# LAMEBOY.net
KiCad netlist of a schematic drawn in EAGLE
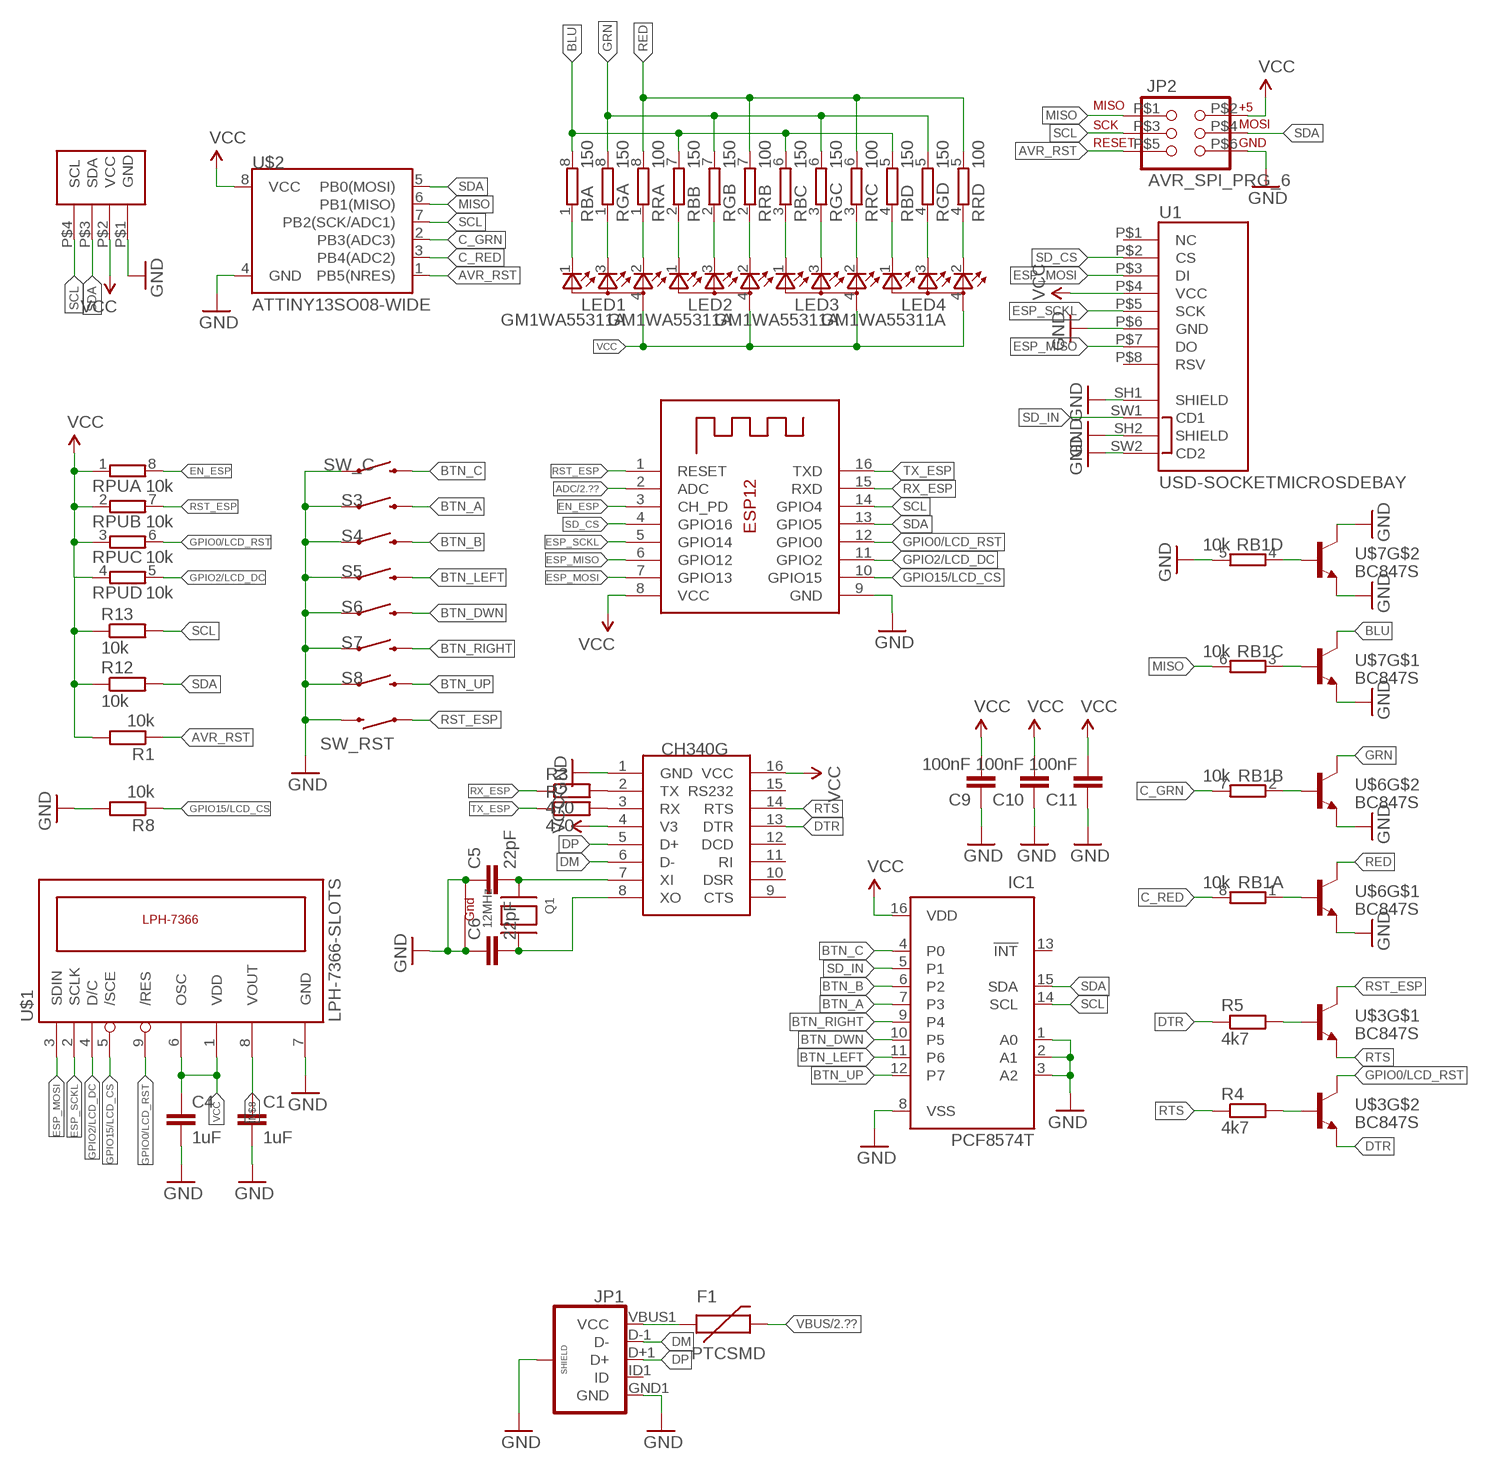
[diagram p0: schematic, sheet 1]
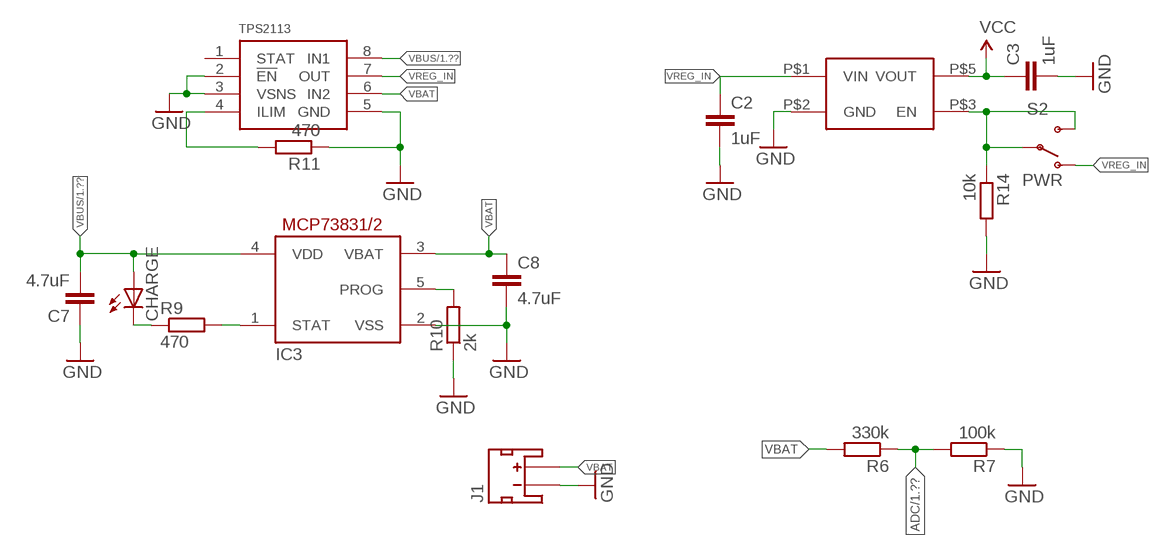
[diagram p1: schematic, sheet 2]

(export (version "E")
  (design (tool "Eeschema 10.0.6"))
  (components
    (comp (ref "C2")
      (value "1uF")
      (footprint "eagle-import:ONEFITSALL")
      (libsource (lib "eagle-import") (part "C-EUONEFITSALL"))
    )
    (comp (ref "C3")
      (value "1uF")
      (footprint "eagle-import:ONEFITSALL")
      (libsource (lib "eagle-import") (part "C-EUONEFITSALL"))
    )
    (comp (ref "C7")
      (value "4.7uF")
      (footprint "eagle-import:ONEFITSALL")
      (libsource (lib "eagle-import") (part "C-EUONEFITSALL"))
    )
    (comp (ref "C8")
      (value "4.7uF")
      (footprint "eagle-import:ONEFITSALL")
      (libsource (lib "eagle-import") (part "C-EUONEFITSALL"))
    )
    (comp (ref "CHARGE")
      (value "LEDCHARLIE")
      (footprint "eagle-import:CHIPLED_0603_CHARLIE")
      (libsource (lib "eagle-import") (part "LEDCHARLIE"))
    )
    (comp (ref "IC3")
      (value "MCP73831")
      (footprint "eagle-import:SOT23-5L")
      (libsource (lib "eagle-import") (part "MCP73831/OT"))
    )
    (comp (ref "J1")
      (value "JST_2MM_MALE")
      (footprint "eagle-import:JST-2-SMD")
      (libsource (lib "eagle-import") (part "JST_2MM_MALE"))
    )
    (comp (ref "R6")
      (value "330k")
      (footprint "eagle-import:ONEFITSALL")
      (libsource (lib "eagle-import") (part "R-EU_ONEFITSALL"))
    )
    (comp (ref "R7")
      (value "100k")
      (footprint "eagle-import:ONEFITSALL")
      (libsource (lib "eagle-import") (part "R-EU_ONEFITSALL"))
    )
    (comp (ref "R9")
      (value "470")
      (footprint "eagle-import:ONEFITSALL")
      (libsource (lib "eagle-import") (part "R-EU_ONEFITSALL"))
    )
    (comp (ref "R10")
      (value "2k")
      (footprint "eagle-import:ONEFITSALL")
      (libsource (lib "eagle-import") (part "R-EU_ONEFITSALL"))
    )
    (comp (ref "R11")
      (value "470")
      (footprint "eagle-import:ONEFITSALL")
      (libsource (lib "eagle-import") (part "R-EU_ONEFITSALL"))
    )
    (comp (ref "R14")
      (value "10k")
      (footprint "eagle-import:ONEFITSALL")
      (libsource (lib "eagle-import") (part "R-EU_ONEFITSALL"))
    )
    (comp (ref "S2")
      (value "PWR")
      (footprint "eagle-import:SWITCH-SPST-SMD-A")
      (libsource (lib "eagle-import") (part "SWITCH-SPDT-SMD-A"))
    )
    (comp (ref "U$4")
      (value "TPS2113-PW")
      (footprint "eagle-import:TEXAS-PW")
      (libsource (lib "eagle-import") (part "TPS2113-PW"))
    )
    (comp (ref "U$9")
      (value "AP2112KAP2112K")
      (footprint "eagle-import:AP2112")
      (libsource (lib "eagle-import") (part "AP2112KAP2112K"))
    )
    (comp (ref "C1")
      (value "1uF")
      (footprint "eagle-import:ONEFITSALL")
      (libsource (lib "eagle-import") (part "C-EUONEFITSALL"))
    )
    (comp (ref "C4")
      (value "1uF")
      (footprint "eagle-import:ONEFITSALL")
      (libsource (lib "eagle-import") (part "C-EUONEFITSALL"))
    )
    (comp (ref "C5")
      (value "22pF")
      (footprint "eagle-import:ONEFITSALL")
      (libsource (lib "eagle-import") (part "C-EUONEFITSALL"))
    )
    (comp (ref "C6")
      (value "22pF")
      (footprint "eagle-import:ONEFITSALL")
      (libsource (lib "eagle-import") (part "C-EUONEFITSALL"))
    )
    (comp (ref "C9")
      (value "100nF")
      (footprint "eagle-import:ONEFITSALL")
      (libsource (lib "eagle-import") (part "C-EUONEFITSALL"))
    )
    (comp (ref "C10")
      (value "100nF")
      (footprint "eagle-import:ONEFITSALL")
      (libsource (lib "eagle-import") (part "C-EUONEFITSALL"))
    )
    (comp (ref "C11")
      (value "100nF")
      (footprint "eagle-import:ONEFITSALL")
      (libsource (lib "eagle-import") (part "C-EUONEFITSALL"))
    )
    (comp (ref "CH340G")
      (value "CH340GCH340G")
      (footprint "eagle-import:SOIC16")
      (libsource (lib "eagle-import") (part "CH340GCH340G"))
    )
    (comp (ref "F1")
      (value "PTCSMD")
      (footprint "eagle-import:PTC-1206")
      (libsource (lib "eagle-import") (part "PTCSMD"))
    )
    (comp (ref "IC1")
      (value "PCF8574T")
      (footprint "eagle-import:SO16W")
      (fields (field (name "MPN") "PCF8574T/3,512"))
      (libsource (lib "eagle-import") (part "PCF8574T"))
    )
    (comp (ref "JP1")
      (value "USB_MICROB_PLUG-IDK")
      (footprint "eagle-import:USB-AB-MICRO-SMD_SLOT")
      (libsource (lib "eagle-import") (part "USB_MICROB_PLUG-IDK"))
    )
    (comp (ref "JP2")
      (value "AVR_SPI_PRG_6")
      (footprint "eagle-import:2X3_SMD_PAD")
      (libsource (lib "eagle-import") (part "AVR_SPI_PRG_6"))
    )
    (comp (ref "LED1")
      (value "GM1WA55311A")
      (footprint "eagle-import:GM1WA55311A")
      (libsource (lib "eagle-import") (part "GM1WA55311A"))
    )
    (comp (ref "LED2")
      (value "GM1WA55311A")
      (footprint "eagle-import:GM1WA55311A")
      (libsource (lib "eagle-import") (part "GM1WA55311A"))
    )
    (comp (ref "LED3")
      (value "GM1WA55311A")
      (footprint "eagle-import:GM1WA55311A")
      (libsource (lib "eagle-import") (part "GM1WA55311A"))
    )
    (comp (ref "LED4")
      (value "GM1WA55311A")
      (footprint "eagle-import:GM1WA55311A")
      (libsource (lib "eagle-import") (part "GM1WA55311A"))
    )
    (comp (ref "Q1")
      (value "12MHz")
      (footprint "eagle-import:NX3225_BIGGER")
      (libsource (lib "eagle-import") (part "XTAL-4BIGGER"))
    )
    (comp (ref "R1")
      (value "10k")
      (footprint "eagle-import:ONEFITSALL")
      (libsource (lib "eagle-import") (part "R-EU_ONEFITSALL"))
    )
    (comp (ref "R2")
      (value "470")
      (footprint "eagle-import:ONEFITSALL")
      (libsource (lib "eagle-import") (part "R-EU_ONEFITSALL"))
    )
    (comp (ref "R3")
      (value "470")
      (footprint "eagle-import:ONEFITSALL")
      (libsource (lib "eagle-import") (part "R-EU_ONEFITSALL"))
    )
    (comp (ref "R4")
      (value "4k7")
      (footprint "eagle-import:ONEFITSALL")
      (libsource (lib "eagle-import") (part "R-EU_ONEFITSALL"))
    )
    (comp (ref "R5")
      (value "4k7")
      (footprint "eagle-import:ONEFITSALL")
      (libsource (lib "eagle-import") (part "R-EU_ONEFITSALL"))
    )
    (comp (ref "R8")
      (value "10k")
      (footprint "eagle-import:ONEFITSALL")
      (libsource (lib "eagle-import") (part "R-EU_ONEFITSALL"))
    )
    (comp (ref "R12")
      (value "10k")
      (footprint "eagle-import:ONEFITSALL")
      (libsource (lib "eagle-import") (part "R-EU_ONEFITSALL"))
    )
    (comp (ref "R13")
      (value "10k")
      (footprint "eagle-import:ONEFITSALL")
      (libsource (lib "eagle-import") (part "R-EU_ONEFITSALL"))
    )
    (comp (ref "RB")
      (value "150")
      (footprint "eagle-import:0603-ARC")
      (libsource (lib "eagle-import") (part "4R-N0603-ARC"))
    )
    (comp (ref "RB1")
      (value "10k")
      (footprint "eagle-import:0603-ARC")
      (libsource (lib "eagle-import") (part "4R-N0603-ARC"))
    )
    (comp (ref "RG")
      (value "150")
      (footprint "eagle-import:0603-ARC")
      (libsource (lib "eagle-import") (part "4R-N0603-ARC"))
    )
    (comp (ref "RPU")
      (value "10k")
      (footprint "eagle-import:0603-ARC")
      (libsource (lib "eagle-import") (part "4R-N0603-ARC"))
    )
    (comp (ref "RR")
      (value "100")
      (footprint "eagle-import:0603-ARC")
      (libsource (lib "eagle-import") (part "4R-N0603-ARC"))
    )
    (comp (ref "S3")
      (value "SWITCH-MOMENTARY-2SMD-4")
      (footprint "eagle-import:TACTILE_SWITCH_TALL")
      (libsource (lib "eagle-import") (part "SWITCH-MOMENTARY-2SMD-4"))
    )
    (comp (ref "S4")
      (value "SWITCH-MOMENTARY-2SMD-4")
      (footprint "eagle-import:TACTILE_SWITCH_TALL")
      (libsource (lib "eagle-import") (part "SWITCH-MOMENTARY-2SMD-4"))
    )
    (comp (ref "S5")
      (value "SWITCH-MOMENTARY-2SMD-4")
      (footprint "eagle-import:TACTILE_SWITCH_TALL")
      (libsource (lib "eagle-import") (part "SWITCH-MOMENTARY-2SMD-4"))
    )
    (comp (ref "S6")
      (value "SWITCH-MOMENTARY-2SMD-4")
      (footprint "eagle-import:TACTILE_SWITCH_TALL")
      (libsource (lib "eagle-import") (part "SWITCH-MOMENTARY-2SMD-4"))
    )
    (comp (ref "S7")
      (value "SWITCH-MOMENTARY-2SMD-4")
      (footprint "eagle-import:TACTILE_SWITCH_TALL")
      (libsource (lib "eagle-import") (part "SWITCH-MOMENTARY-2SMD-4"))
    )
    (comp (ref "S8")
      (value "SWITCH-MOMENTARY-2SMD-4")
      (footprint "eagle-import:TACTILE_SWITCH_TALL")
      (libsource (lib "eagle-import") (part "SWITCH-MOMENTARY-2SMD-4"))
    )
    (comp (ref "SW_C")
      (value "SWITCH-MOMENTARY-2-SMD-1101NE")
      (footprint "eagle-import:TACTILE-SWITCH-1101NE")
      (libsource (lib "eagle-import") (part "SWITCH-MOMENTARY-2-SMD-1101NE"))
    )
    (comp (ref "SW_RST")
      (value "SWITCH-MOMENTARY-2-SMD-1101NE")
      (footprint "eagle-import:TACTILE-SWITCH-1101NE")
      (libsource (lib "eagle-import") (part "SWITCH-MOMENTARY-2-SMD-1101NE"))
    )
    (comp (ref "U$1")
      (value "LPH-7366-SLOTS")
      (footprint "eagle-import:LPH-7366-SLOTS")
      (libsource (lib "eagle-import") (part "LPH-7366-SLOTS"))
    )
    (comp (ref "U$2")
      (value "ATTINY13SO08-WIDE")
      (footprint "eagle-import:SO08-EIAJ")
      (libsource (lib "eagle-import") (part "ATTINY13SO08-WIDE"))
    )
    (comp (ref "U$3")
      (value "BC847S")
      (footprint "eagle-import:SOT363")
      (libsource (lib "eagle-import") (part "MMDT3904"))
    )
    (comp (ref "U$6")
      (value "BC847S")
      (footprint "eagle-import:SOT363")
      (libsource (lib "eagle-import") (part "MMDT3904"))
    )
    (comp (ref "U$7")
      (value "BC847S")
      (footprint "eagle-import:SOT363")
      (libsource (lib "eagle-import") (part "MMDT3904"))
    )
    (comp (ref "U$10")
      (value "I2C_GROVE")
      (footprint "eagle-import:I2C_GROVE")
      (libsource (lib "eagle-import") (part "I2C_GROVE"))
    )
    (comp (ref "U1")
      (value "USD-SOCKETMICROSDEBAY")
      (footprint "eagle-import:MICRO-SD-SOCKET-EBAY")
      (libsource (lib "eagle-import") (part "USD-SOCKETMICROSDEBAY"))
    )
    (comp (ref "X1")
      (value "ESP-12")
      (footprint "eagle-import:ESP-12")
      (libsource (lib "eagle-import") (part "ESP-12"))
    )
  )
  (nets
    (net (code "1") (name "ADC") (class "Default")
      (node (ref "R6") (pin "P$1") (pinfunction "1_P$1") (pintype "passive"))
      (node (ref "R7") (pin "P$2") (pinfunction "2_P$2") (pintype "passive"))
      (node (ref "X1") (pin "2") (pinfunction "ADC_2") (pintype "passive"))
    )
    (net (code "2") (name "AVR_RST") (class "Default")
      (node (ref "JP2") (pin "P$5") (pinfunction "5_P$5") (pintype "passive"))
      (node (ref "R1") (pin "P$1") (pinfunction "1_P$1") (pintype "passive"))
      (node (ref "U$2") (pin "1") (pinfunction "PB5(NRES)_1") (pintype "bidirectional"))
    )
    (net (code "3") (name "BLU") (class "Default")
      (node (ref "RB") (pin "5") (pinfunction "2_5") (pintype "passive"))
      (node (ref "RB") (pin "6") (pinfunction "2_6") (pintype "passive"))
      (node (ref "RB") (pin "7") (pinfunction "2_7") (pintype "passive"))
      (node (ref "RB") (pin "8") (pinfunction "2_8") (pintype "passive"))
      (node (ref "U$7") (pin "3") (pinfunction "C_3") (pintype "passive"))
    )
    (net (code "4") (name "BTN_A") (class "Default")
      (node (ref "IC1") (pin "7") (pinfunction "P3_7") (pintype "bidirectional"))
      (node (ref "S3") (pin "B2") (pinfunction "2_B2") (pintype "passive"))
    )
    (net (code "5") (name "BTN_B") (class "Default")
      (node (ref "IC1") (pin "6") (pinfunction "P2_6") (pintype "bidirectional"))
      (node (ref "S4") (pin "B2") (pinfunction "2_B2") (pintype "passive"))
    )
    (net (code "6") (name "BTN_C") (class "Default")
      (node (ref "IC1") (pin "4") (pinfunction "P0_4") (pintype "bidirectional"))
      (node (ref "SW_C") (pin "P$2") (pinfunction "2_P$2") (pintype "passive"))
    )
    (net (code "7") (name "BTN_DWN") (class "Default")
      (node (ref "IC1") (pin "10") (pinfunction "P5_10") (pintype "bidirectional"))
      (node (ref "S6") (pin "B2") (pinfunction "2_B2") (pintype "passive"))
    )
    (net (code "8") (name "BTN_LEFT") (class "Default")
      (node (ref "IC1") (pin "11") (pinfunction "P6_11") (pintype "bidirectional"))
      (node (ref "S5") (pin "B2") (pinfunction "2_B2") (pintype "passive"))
    )
    (net (code "9") (name "BTN_RIGHT") (class "Default")
      (node (ref "IC1") (pin "9") (pinfunction "P4_9") (pintype "bidirectional"))
      (node (ref "S7") (pin "B2") (pinfunction "2_B2") (pintype "passive"))
    )
    (net (code "10") (name "BTN_UP") (class "Default")
      (node (ref "IC1") (pin "12") (pinfunction "P7_12") (pintype "bidirectional"))
      (node (ref "S8") (pin "B2") (pinfunction "2_B2") (pintype "passive"))
    )
    (net (code "11") (name "C_GRN") (class "Default")
      (node (ref "RB1") (pin "7") (pinfunction "2_7") (pintype "passive"))
      (node (ref "U$2") (pin "2") (pinfunction "PB3(ADC3)_2") (pintype "bidirectional"))
    )
    (net (code "12") (name "C_RED") (class "Default")
      (node (ref "RB1") (pin "8") (pinfunction "2_8") (pintype "passive"))
      (node (ref "U$2") (pin "3") (pinfunction "PB4(ADC2)_3") (pintype "bidirectional"))
    )
    (net (code "13") (name "DM") (class "Default")
      (node (ref "CH340G") (pin "6") (pinfunction "D-_6") (pintype "bidirectional"))
      (node (ref "JP1") (pin "D-1") (pinfunction "D-_D-1") (pintype "bidirectional"))
    )
    (net (code "14") (name "DP") (class "Default")
      (node (ref "CH340G") (pin "5") (pinfunction "D+_5") (pintype "bidirectional"))
      (node (ref "JP1") (pin "D+1") (pinfunction "D+_D+1") (pintype "bidirectional"))
    )
    (net (code "15") (name "DTR") (class "Default")
      (node (ref "CH340G") (pin "13") (pinfunction "DTR_13") (pintype "bidirectional"))
      (node (ref "R5") (pin "P$1") (pinfunction "1_P$1") (pintype "passive"))
      (node (ref "U$3") (pin "1") (pinfunction "E_1") (pintype "passive"))
    )
    (net (code "16") (name "EN_ESP") (class "Default")
      (node (ref "RPU") (pin "8") (pinfunction "2_8") (pintype "passive"))
      (node (ref "X1") (pin "3") (pinfunction "CH_PD_3") (pintype "input"))
    )
    (net (code "17") (name "ESP_MISO") (class "Default")
      (node (ref "U1") (pin "P$7") (pinfunction "DO_P$7") (pintype "bidirectional"))
      (node (ref "X1") (pin "6") (pinfunction "GPIO12_6") (pintype "bidirectional"))
    )
    (net (code "18") (name "ESP_MOSI") (class "Default")
      (node (ref "U$1") (pin "3") (pinfunction "SDIN_3") (pintype "input"))
      (node (ref "U1") (pin "P$3") (pinfunction "DI_P$3") (pintype "bidirectional"))
      (node (ref "X1") (pin "7") (pinfunction "GPIO13_7") (pintype "bidirectional"))
    )
    (net (code "19") (name "ESP_SCKL") (class "Default")
      (node (ref "U$1") (pin "2") (pinfunction "SCLK_2") (pintype "input"))
      (node (ref "U1") (pin "P$5") (pinfunction "SCK_P$5") (pintype "bidirectional"))
      (node (ref "X1") (pin "5") (pinfunction "GPIO14_5") (pintype "bidirectional"))
    )
    (net (code "20") (name "GND") (class "Default")
      (node (ref "C1") (pin "P$2") (pinfunction "2_P$2") (pintype "passive"))
      (node (ref "C10") (pin "P$1") (pinfunction "1_P$1") (pintype "passive"))
      (node (ref "C11") (pin "P$1") (pinfunction "1_P$1") (pintype "passive"))
      (node (ref "C2") (pin "P$2") (pinfunction "2_P$2") (pintype "passive"))
      (node (ref "C3") (pin "P$2") (pinfunction "2_P$2") (pintype "passive"))
      (node (ref "C4") (pin "P$2") (pinfunction "2_P$2") (pintype "passive"))
      (node (ref "C5") (pin "P$1") (pinfunction "1_P$1") (pintype "passive"))
      (node (ref "C6") (pin "P$1") (pinfunction "1_P$1") (pintype "passive"))
      (node (ref "C7") (pin "P$1") (pinfunction "1_P$1") (pintype "passive"))
      (node (ref "C8") (pin "P$2") (pinfunction "2_P$2") (pintype "passive"))
      (node (ref "C9") (pin "P$1") (pinfunction "1_P$1") (pintype "passive"))
      (node (ref "CH340G") (pin "1") (pinfunction "GND_1") (pintype "bidirectional"))
      (node (ref "IC1") (pin "1") (pinfunction "A0_1") (pintype "input"))
      (node (ref "IC1") (pin "2") (pinfunction "A1_2") (pintype "input"))
      (node (ref "IC1") (pin "3") (pinfunction "A2_3") (pintype "input"))
      (node (ref "IC1") (pin "8") (pinfunction "VSS_8") (pintype "power_in"))
      (node (ref "IC3") (pin "2") (pinfunction "VSS_2") (pintype "power_in"))
      (node (ref "J1") (pin "1") (pinfunction "-_1") (pintype "bidirectional"))
      (node (ref "JP1") (pin "GND1") (pinfunction "GND_GND1") (pintype "bidirectional"))
      (node (ref "JP1") (pin "P$1") (pinfunction "SHIELD_P$1") (pintype "bidirectional"))
      (node (ref "JP1") (pin "P$2") (pinfunction "SHIELD_P$2") (pintype "bidirectional"))
      (node (ref "JP1") (pin "P$3") (pinfunction "SHIELD_P$3") (pintype "bidirectional"))
      (node (ref "JP1") (pin "P$4") (pinfunction "SHIELD_P$4") (pintype "bidirectional"))
      (node (ref "JP2") (pin "P$6") (pinfunction "6_P$6") (pintype "passive"))
      (node (ref "Q1") (pin "2") (pinfunction "G2_2") (pintype "power_in"))
      (node (ref "Q1") (pin "4") (pinfunction "G1_4") (pintype "power_in"))
      (node (ref "R10") (pin "P$1") (pinfunction "1_P$1") (pintype "passive"))
      (node (ref "R11") (pin "P$1") (pinfunction "1_P$1") (pintype "passive"))
      (node (ref "R14") (pin "P$2") (pinfunction "2_P$2") (pintype "passive"))
      (node (ref "R7") (pin "P$1") (pinfunction "1_P$1") (pintype "passive"))
      (node (ref "R8") (pin "P$2") (pinfunction "2_P$2") (pintype "passive"))
      (node (ref "RB1") (pin "5") (pinfunction "2_5") (pintype "passive"))
      (node (ref "S3") (pin "A2") (pinfunction "1_A2") (pintype "passive"))
      (node (ref "S4") (pin "A2") (pinfunction "1_A2") (pintype "passive"))
      (node (ref "S5") (pin "A2") (pinfunction "1_A2") (pintype "passive"))
      (node (ref "S6") (pin "A2") (pinfunction "1_A2") (pintype "passive"))
      (node (ref "S7") (pin "A2") (pinfunction "1_A2") (pintype "passive"))
      (node (ref "S8") (pin "A2") (pinfunction "1_A2") (pintype "passive"))
      (node (ref "SW_C") (pin "P$1") (pinfunction "1_P$1") (pintype "passive"))
      (node (ref "SW_RST") (pin "P$2") (pinfunction "2_P$2") (pintype "passive"))
      (node (ref "U$1") (pin "7") (pinfunction "GND_7") (pintype "power_in"))
      (node (ref "U$10") (pin "P$1") (pinfunction "GND_P$1") (pintype "bidirectional"))
      (node (ref "U$2") (pin "4") (pinfunction "GND_4") (pintype "bidirectional"))
      (node (ref "U$4") (pin "2") (pinfunction "~{EN}_2") (pintype "bidirectional"))
      (node (ref "U$4") (pin "3") (pinfunction "VSNS_3") (pintype "bidirectional"))
      (node (ref "U$4") (pin "5") (pinfunction "GND_5") (pintype "bidirectional"))
      (node (ref "U$6") (pin "1") (pinfunction "E_1") (pintype "passive"))
      (node (ref "U$6") (pin "4") (pinfunction "E_4") (pintype "passive"))
      (node (ref "U$7") (pin "1") (pinfunction "E_1") (pintype "passive"))
      (node (ref "U$7") (pin "4") (pinfunction "E_4") (pintype "passive"))
      (node (ref "U$7") (pin "6") (pinfunction "C_6") (pintype "passive"))
      (node (ref "U$9") (pin "P$2") (pinfunction "GND_P$2") (pintype "bidirectional"))
      (node (ref "U1") (pin "P$6") (pinfunction "GND_P$6") (pintype "bidirectional"))
      (node (ref "U1") (pin "SH1") (pinfunction "SHIELD_SH1") (pintype "bidirectional"))
      (node (ref "U1") (pin "SH2") (pinfunction "SHIELD_SH2") (pintype "bidirectional"))
      (node (ref "U1") (pin "SW2") (pinfunction "CD2_SW2") (pintype "bidirectional"))
      (node (ref "X1") (pin "9") (pinfunction "GND_9") (pintype "power_in"))
    )
    (net (code "21") (name "GPIO0{slash}LCD_RST") (class "Default")
      (node (ref "RPU") (pin "6") (pinfunction "2_6") (pintype "passive"))
      (node (ref "U$1") (pin "9") (pinfunction "/RES_9") (pintype "input"))
      (node (ref "U$3") (pin "6") (pinfunction "C_6") (pintype "passive"))
      (node (ref "X1") (pin "12") (pinfunction "GPIO0_12") (pintype "bidirectional"))
    )
    (net (code "22") (name "GPIO2{slash}LCD_DC") (class "Default")
      (node (ref "RPU") (pin "5") (pinfunction "2_5") (pintype "passive"))
      (node (ref "U$1") (pin "4") (pinfunction "D/C_4") (pintype "input"))
      (node (ref "X1") (pin "11") (pinfunction "GPIO2_11") (pintype "bidirectional"))
    )
    (net (code "23") (name "GPIO15{slash}LCD_CS") (class "Default")
      (node (ref "R8") (pin "P$1") (pinfunction "1_P$1") (pintype "passive"))
      (node (ref "U$1") (pin "5") (pinfunction "/SCE_5") (pintype "input"))
      (node (ref "X1") (pin "10") (pinfunction "GPIO15_10") (pintype "bidirectional"))
    )
    (net (code "24") (name "GRN") (class "Default")
      (node (ref "RG") (pin "5") (pinfunction "2_5") (pintype "passive"))
      (node (ref "RG") (pin "6") (pinfunction "2_6") (pintype "passive"))
      (node (ref "RG") (pin "7") (pinfunction "2_7") (pintype "passive"))
      (node (ref "RG") (pin "8") (pinfunction "2_8") (pintype "passive"))
      (node (ref "U$6") (pin "6") (pinfunction "C_6") (pintype "passive"))
    )
    (net (code "25") (name "MISO") (class "Default")
      (node (ref "JP2") (pin "P$1") (pinfunction "1_P$1") (pintype "passive"))
      (node (ref "RB1") (pin "6") (pinfunction "2_6") (pintype "passive"))
      (node (ref "U$2") (pin "6") (pinfunction "PB1(MISO)_6") (pintype "bidirectional"))
    )
    (net (code "26") (name "N$8") (class "Default")
      (node (ref "C1") (pin "P$1") (pinfunction "1_P$1") (pintype "passive"))
      (node (ref "U$1") (pin "8") (pinfunction "VOUT_8") (pintype "passive"))
    )
    (net (code "27") (name "Net-(C5-2)") (class "Default")
      (node (ref "C5") (pin "P$2") (pinfunction "2_P$2") (pintype "passive"))
      (node (ref "CH340G") (pin "7") (pinfunction "XI_7") (pintype "bidirectional"))
      (node (ref "Q1") (pin "1") (pinfunction "X1_1") (pintype "bidirectional"))
    )
    (net (code "28") (name "Net-(C6-2)") (class "Default")
      (node (ref "C6") (pin "P$2") (pinfunction "2_P$2") (pintype "passive"))
      (node (ref "CH340G") (pin "8") (pinfunction "XO_8") (pintype "bidirectional"))
      (node (ref "Q1") (pin "3") (pinfunction "X2_3") (pintype "bidirectional"))
    )
    (net (code "29") (name "Net-(CH340G-RX)") (class "Default")
      (node (ref "CH340G") (pin "3") (pinfunction "RX_3") (pintype "bidirectional"))
      (node (ref "R2") (pin "P$2") (pinfunction "2_P$2") (pintype "passive"))
    )
    (net (code "30") (name "Net-(CH340G-TX)") (class "Default")
      (node (ref "CH340G") (pin "2") (pinfunction "TX_2") (pintype "bidirectional"))
      (node (ref "R3") (pin "P$2") (pinfunction "2_P$2") (pintype "passive"))
    )
    (net (code "31") (name "Net-(IC3-PROG)") (class "Default")
      (node (ref "IC3") (pin "5") (pinfunction "PROG_5") (pintype "input"))
      (node (ref "R10") (pin "P$2") (pinfunction "2_P$2") (pintype "passive"))
    )
    (net (code "32") (name "Net-(IC3-STAT)") (class "Default")
      (node (ref "IC3") (pin "1") (pinfunction "STAT_1") (pintype "output"))
      (node (ref "R9") (pin "P$2") (pinfunction "2_P$2") (pintype "passive"))
    )
    (net (code "33") (name "Net-(JP1-VCC)") (class "Default")
      (node (ref "F1") (pin "1") (pinfunction "1_1") (pintype "bidirectional"))
      (node (ref "JP1") (pin "VBUS1") (pinfunction "VCC_VBUS1") (pintype "bidirectional"))
    )
    (net (code "34") (name "Net-(LED1-CBLUE)") (class "Default")
      (node (ref "LED1") (pin "3") (pinfunction "CBLUE_3") (pintype "passive"))
      (node (ref "RG") (pin "1") (pinfunction "1_1") (pintype "passive"))
    )
    (net (code "35") (name "Net-(LED1-CGREEN)") (class "Default")
      (node (ref "LED1") (pin "1") (pinfunction "CGREEN_1") (pintype "passive"))
      (node (ref "RB") (pin "1") (pinfunction "1_1") (pintype "passive"))
    )
    (net (code "36") (name "Net-(LED1-CRED)") (class "Default")
      (node (ref "LED1") (pin "2") (pinfunction "CRED_2") (pintype "passive"))
      (node (ref "RR") (pin "1") (pinfunction "1_1") (pintype "passive"))
    )
    (net (code "37") (name "Net-(LED2-CBLUE)") (class "Default")
      (node (ref "LED2") (pin "3") (pinfunction "CBLUE_3") (pintype "passive"))
      (node (ref "RG") (pin "2") (pinfunction "1_2") (pintype "passive"))
    )
    (net (code "38") (name "Net-(LED2-CGREEN)") (class "Default")
      (node (ref "LED2") (pin "1") (pinfunction "CGREEN_1") (pintype "passive"))
      (node (ref "RB") (pin "2") (pinfunction "1_2") (pintype "passive"))
    )
    (net (code "39") (name "Net-(LED2-CRED)") (class "Default")
      (node (ref "LED2") (pin "2") (pinfunction "CRED_2") (pintype "passive"))
      (node (ref "RR") (pin "2") (pinfunction "1_2") (pintype "passive"))
    )
    (net (code "40") (name "Net-(LED3-CBLUE)") (class "Default")
      (node (ref "LED3") (pin "3") (pinfunction "CBLUE_3") (pintype "passive"))
      (node (ref "RG") (pin "3") (pinfunction "1_3") (pintype "passive"))
    )
    (net (code "41") (name "Net-(LED3-CGREEN)") (class "Default")
      (node (ref "LED3") (pin "1") (pinfunction "CGREEN_1") (pintype "passive"))
      (node (ref "RB") (pin "3") (pinfunction "1_3") (pintype "passive"))
    )
    (net (code "42") (name "Net-(LED3-CRED)") (class "Default")
      (node (ref "LED3") (pin "2") (pinfunction "CRED_2") (pintype "passive"))
      (node (ref "RR") (pin "3") (pinfunction "1_3") (pintype "passive"))
    )
    (net (code "43") (name "Net-(LED4-CBLUE)") (class "Default")
      (node (ref "LED4") (pin "3") (pinfunction "CBLUE_3") (pintype "passive"))
      (node (ref "RG") (pin "4") (pinfunction "1_4") (pintype "passive"))
    )
    (net (code "44") (name "Net-(LED4-CGREEN)") (class "Default")
      (node (ref "LED4") (pin "1") (pinfunction "CGREEN_1") (pintype "passive"))
      (node (ref "RB") (pin "4") (pinfunction "1_4") (pintype "passive"))
    )
    (net (code "45") (name "Net-(LED4-CRED)") (class "Default")
      (node (ref "LED4") (pin "2") (pinfunction "CRED_2") (pintype "passive"))
      (node (ref "RR") (pin "4") (pinfunction "1_4") (pintype "passive"))
    )
    (net (code "46") (name "Net-(R4-2)") (class "Default")
      (node (ref "R4") (pin "P$2") (pinfunction "2_P$2") (pintype "passive"))
      (node (ref "U$3") (pin "2") (pinfunction "B_2") (pintype "passive"))
    )
    (net (code "47") (name "Net-(R5-2)") (class "Default")
      (node (ref "R5") (pin "P$2") (pinfunction "2_P$2") (pintype "passive"))
      (node (ref "U$3") (pin "5") (pinfunction "B_5") (pintype "passive"))
    )
    (net (code "48") (name "Net-(R9-1)") (class "Default")
      (node (ref "CHARGE") (pin "C") (pinfunction "C_C") (pintype "passive"))
      (node (ref "R9") (pin "P$1") (pinfunction "1_P$1") (pintype "passive"))
    )
    (net (code "49") (name "Net-(R11-2)") (class "Default")
      (node (ref "R11") (pin "P$2") (pinfunction "2_P$2") (pintype "passive"))
      (node (ref "U$4") (pin "4") (pinfunction "ILIM_4") (pintype "bidirectional"))
    )
    (net (code "50") (name "Net-(R14-1)") (class "Default")
      (node (ref "R14") (pin "P$1") (pinfunction "1_P$1") (pintype "passive"))
      (node (ref "S2") (pin "2") (pinfunction "P_2") (pintype "passive"))
      (node (ref "S2") (pin "3") (pinfunction "S_3") (pintype "passive"))
      (node (ref "U$9") (pin "P$3") (pinfunction "EN_P$3") (pintype "bidirectional"))
    )
    (net (code "51") (name "Net-(RB1B-1)") (class "Default")
      (node (ref "RB1") (pin "2") (pinfunction "1_2") (pintype "passive"))
      (node (ref "U$6") (pin "2") (pinfunction "B_2") (pintype "passive"))
    )
    (net (code "52") (name "Net-(RB1C-1)") (class "Default")
      (node (ref "RB1") (pin "3") (pinfunction "1_3") (pintype "passive"))
      (node (ref "U$7") (pin "5") (pinfunction "B_5") (pintype "passive"))
    )
    (net (code "53") (name "Net-(RB1D-1)") (class "Default")
      (node (ref "RB1") (pin "4") (pinfunction "1_4") (pintype "passive"))
      (node (ref "U$7") (pin "2") (pinfunction "B_2") (pintype "passive"))
    )
    (net (code "54") (name "Net-(U$6A-B)") (class "Default")
      (node (ref "RB1") (pin "1") (pinfunction "1_1") (pintype "passive"))
      (node (ref "U$6") (pin "5") (pinfunction "B_5") (pintype "passive"))
    )
    (net (code "55") (name "RED") (class "Default")
      (node (ref "RR") (pin "5") (pinfunction "2_5") (pintype "passive"))
      (node (ref "RR") (pin "6") (pinfunction "2_6") (pintype "passive"))
      (node (ref "RR") (pin "7") (pinfunction "2_7") (pintype "passive"))
      (node (ref "RR") (pin "8") (pinfunction "2_8") (pintype "passive"))
      (node (ref "U$6") (pin "3") (pinfunction "C_3") (pintype "passive"))
    )
    (net (code "56") (name "RST_ESP") (class "Default")
      (node (ref "RPU") (pin "7") (pinfunction "2_7") (pintype "passive"))
      (node (ref "SW_RST") (pin "P$1") (pinfunction "1_P$1") (pintype "passive"))
      (node (ref "U$3") (pin "3") (pinfunction "C_3") (pintype "passive"))
      (node (ref "X1") (pin "1") (pinfunction "RESET_1") (pintype "input"))
    )
    (net (code "57") (name "RTS") (class "Default")
      (node (ref "CH340G") (pin "14") (pinfunction "RTS_14") (pintype "bidirectional"))
      (node (ref "R4") (pin "P$1") (pinfunction "1_P$1") (pintype "passive"))
      (node (ref "U$3") (pin "4") (pinfunction "E_4") (pintype "passive"))
    )
    (net (code "58") (name "RX_ESP") (class "Default")
      (node (ref "R3") (pin "P$1") (pinfunction "1_P$1") (pintype "passive"))
      (node (ref "X1") (pin "15") (pinfunction "RXD_15") (pintype "input"))
    )
    (net (code "59") (name "SCL") (class "Default")
      (node (ref "IC1") (pin "14") (pinfunction "SCL_14") (pintype "input"))
      (node (ref "JP2") (pin "P$3") (pinfunction "3_P$3") (pintype "passive"))
      (node (ref "R13") (pin "P$2") (pinfunction "2_P$2") (pintype "passive"))
      (node (ref "U$10") (pin "P$4") (pinfunction "SCL_P$4") (pintype "bidirectional"))
      (node (ref "U$2") (pin "7") (pinfunction "PB2(SCK/ADC1)_7") (pintype "bidirectional"))
      (node (ref "X1") (pin "14") (pinfunction "GPIO4_14") (pintype "bidirectional"))
    )
    (net (code "60") (name "SDA") (class "Default")
      (node (ref "IC1") (pin "15") (pinfunction "SDA_15") (pintype "bidirectional"))
      (node (ref "JP2") (pin "P$4") (pinfunction "4_P$4") (pintype "passive"))
      (node (ref "R12") (pin "P$2") (pinfunction "2_P$2") (pintype "passive"))
      (node (ref "U$10") (pin "P$3") (pinfunction "SDA_P$3") (pintype "bidirectional"))
      (node (ref "U$2") (pin "5") (pinfunction "PB0(MOSI)_5") (pintype "bidirectional"))
      (node (ref "X1") (pin "13") (pinfunction "GPIO5_13") (pintype "bidirectional"))
    )
    (net (code "61") (name "SD_CS") (class "Default")
      (node (ref "U1") (pin "P$2") (pinfunction "CS_P$2") (pintype "bidirectional"))
      (node (ref "X1") (pin "4") (pinfunction "GPIO16_4") (pintype "bidirectional"))
    )
    (net (code "62") (name "SD_IN") (class "Default")
      (node (ref "IC1") (pin "5") (pinfunction "P1_5") (pintype "bidirectional"))
      (node (ref "U1") (pin "SW1") (pinfunction "CD1_SW1") (pintype "bidirectional"))
    )
    (net (code "63") (name "TX_ESP") (class "Default")
      (node (ref "R2") (pin "P$1") (pinfunction "1_P$1") (pintype "passive"))
      (node (ref "X1") (pin "16") (pinfunction "TXD_16") (pintype "output"))
    )
    (net (code "64") (name "VBAT") (class "Default")
      (node (ref "C8") (pin "P$1") (pinfunction "1_P$1") (pintype "passive"))
      (node (ref "IC3") (pin "3") (pinfunction "VBAT_3") (pintype "bidirectional"))
      (node (ref "J1") (pin "2") (pinfunction "+_2") (pintype "bidirectional"))
      (node (ref "R6") (pin "P$2") (pinfunction "2_P$2") (pintype "passive"))
      (node (ref "U$4") (pin "6") (pinfunction "IN2_6") (pintype "bidirectional"))
    )
    (net (code "65") (name "VBUS") (class "Default")
      (node (ref "C7") (pin "P$2") (pinfunction "2_P$2") (pintype "passive"))
      (node (ref "CHARGE") (pin "A") (pinfunction "A_A") (pintype "passive"))
      (node (ref "F1") (pin "2") (pinfunction "2_2") (pintype "bidirectional"))
      (node (ref "IC3") (pin "4") (pinfunction "VDD_4") (pintype "power_in"))
      (node (ref "U$4") (pin "8") (pinfunction "IN1_8") (pintype "bidirectional"))
    )
    (net (code "66") (name "VCC") (class "Default")
      (node (ref "C10") (pin "P$2") (pinfunction "2_P$2") (pintype "passive"))
      (node (ref "C11") (pin "P$2") (pinfunction "2_P$2") (pintype "passive"))
      (node (ref "C3") (pin "P$1") (pinfunction "1_P$1") (pintype "passive"))
      (node (ref "C4") (pin "P$1") (pinfunction "1_P$1") (pintype "passive"))
      (node (ref "C9") (pin "P$2") (pinfunction "2_P$2") (pintype "passive"))
      (node (ref "CH340G") (pin "16") (pinfunction "VCC_16") (pintype "bidirectional"))
      (node (ref "CH340G") (pin "4") (pinfunction "V3_4") (pintype "bidirectional"))
      (node (ref "IC1") (pin "16") (pinfunction "VDD_16") (pintype "power_in"))
      (node (ref "JP2") (pin "P$2") (pinfunction "2_P$2") (pintype "passive"))
      (node (ref "LED1") (pin "4") (pinfunction "A_4") (pintype "passive"))
      (node (ref "LED2") (pin "4") (pinfunction "A_4") (pintype "passive"))
      (node (ref "LED3") (pin "4") (pinfunction "A_4") (pintype "passive"))
      (node (ref "LED4") (pin "4") (pinfunction "A_4") (pintype "passive"))
      (node (ref "R1") (pin "P$2") (pinfunction "2_P$2") (pintype "passive"))
      (node (ref "R12") (pin "P$1") (pinfunction "1_P$1") (pintype "passive"))
      (node (ref "R13") (pin "P$1") (pinfunction "1_P$1") (pintype "passive"))
      (node (ref "RPU") (pin "1") (pinfunction "1_1") (pintype "passive"))
      (node (ref "RPU") (pin "2") (pinfunction "1_2") (pintype "passive"))
      (node (ref "RPU") (pin "3") (pinfunction "1_3") (pintype "passive"))
      (node (ref "RPU") (pin "4") (pinfunction "1_4") (pintype "passive"))
      (node (ref "U$1") (pin "1") (pinfunction "VDD_1") (pintype "power_in"))
      (node (ref "U$1") (pin "6") (pinfunction "OSC_6") (pintype "passive"))
      (node (ref "U$10") (pin "P$2") (pinfunction "VCC_P$2") (pintype "bidirectional"))
      (node (ref "U$2") (pin "8") (pinfunction "VCC_8") (pintype "bidirectional"))
      (node (ref "U$9") (pin "P$5") (pinfunction "VOUT_P$5") (pintype "bidirectional"))
      (node (ref "U1") (pin "P$4") (pinfunction "VCC_P$4") (pintype "bidirectional"))
      (node (ref "X1") (pin "8") (pinfunction "VCC_8") (pintype "power_in"))
    )
    (net (code "67") (name "VREG_IN") (class "Default")
      (node (ref "C2") (pin "P$1") (pinfunction "1_P$1") (pintype "passive"))
      (node (ref "S2") (pin "1") (pinfunction "O_1") (pintype "passive"))
      (node (ref "U$4") (pin "7") (pinfunction "OUT_7") (pintype "bidirectional"))
      (node (ref "U$9") (pin "P$1") (pinfunction "VIN_P$1") (pintype "bidirectional"))
    )
    (net (code "68") (name "unconnected-(CH340G-CTS-Pad9)") (class "Default")
      (node (ref "CH340G") (pin "9") (pinfunction "CTS_9") (pintype "bidirectional"))
    )
    (net (code "69") (name "unconnected-(CH340G-DCD-Pad12)") (class "Default")
      (node (ref "CH340G") (pin "12") (pinfunction "DCD_12") (pintype "bidirectional"))
    )
    (net (code "70") (name "unconnected-(CH340G-DSR-Pad10)") (class "Default")
      (node (ref "CH340G") (pin "10") (pinfunction "DSR_10") (pintype "bidirectional"))
    )
    (net (code "71") (name "unconnected-(CH340G-RI-Pad11)") (class "Default")
      (node (ref "CH340G") (pin "11") (pinfunction "RI_11") (pintype "bidirectional"))
    )
    (net (code "72") (name "unconnected-(CH340G-RS232-Pad15)") (class "Default")
      (node (ref "CH340G") (pin "15") (pinfunction "RS232_15") (pintype "bidirectional"))
    )
    (net (code "73") (name "unconnected-(IC1-~{INT}-Pad13)") (class "Default")
      (node (ref "IC1") (pin "13") (pinfunction "~{INT}_13") (pintype "output"))
    )
    (net (code "74") (name "unconnected-(J1-PAD1-PadNC1)") (class "Default")
      (node (ref "J1") (pin "NC1") (pinfunction "PAD1_NC1") (pintype "bidirectional"))
    )
    (net (code "75") (name "unconnected-(J1-PAD2-PadNC2)") (class "Default")
      (node (ref "J1") (pin "NC2") (pinfunction "PAD2_NC2") (pintype "bidirectional"))
    )
    (net (code "76") (name "unconnected-(JP1-ID-PadID1)") (class "Default")
      (node (ref "JP1") (pin "ID1") (pinfunction "ID_ID1") (pintype "bidirectional"))
    )
    (net (code "77") (name "unconnected-(U$4-STAT-Pad1)") (class "Default")
      (node (ref "U$4") (pin "1") (pinfunction "STAT_1") (pintype "bidirectional"))
    )
    (net (code "78") (name "unconnected-(U1-NC-PadP$1)") (class "Default")
      (node (ref "U1") (pin "P$1") (pinfunction "NC_P$1") (pintype "bidirectional"))
    )
    (net (code "79") (name "unconnected-(U1-RSV-PadP$8)") (class "Default")
      (node (ref "U1") (pin "P$8") (pinfunction "RSV_P$8") (pintype "bidirectional"))
    )
  )
)
